# single_DPswap.net
KiCad netlist of a schematic drawn in EAGLE
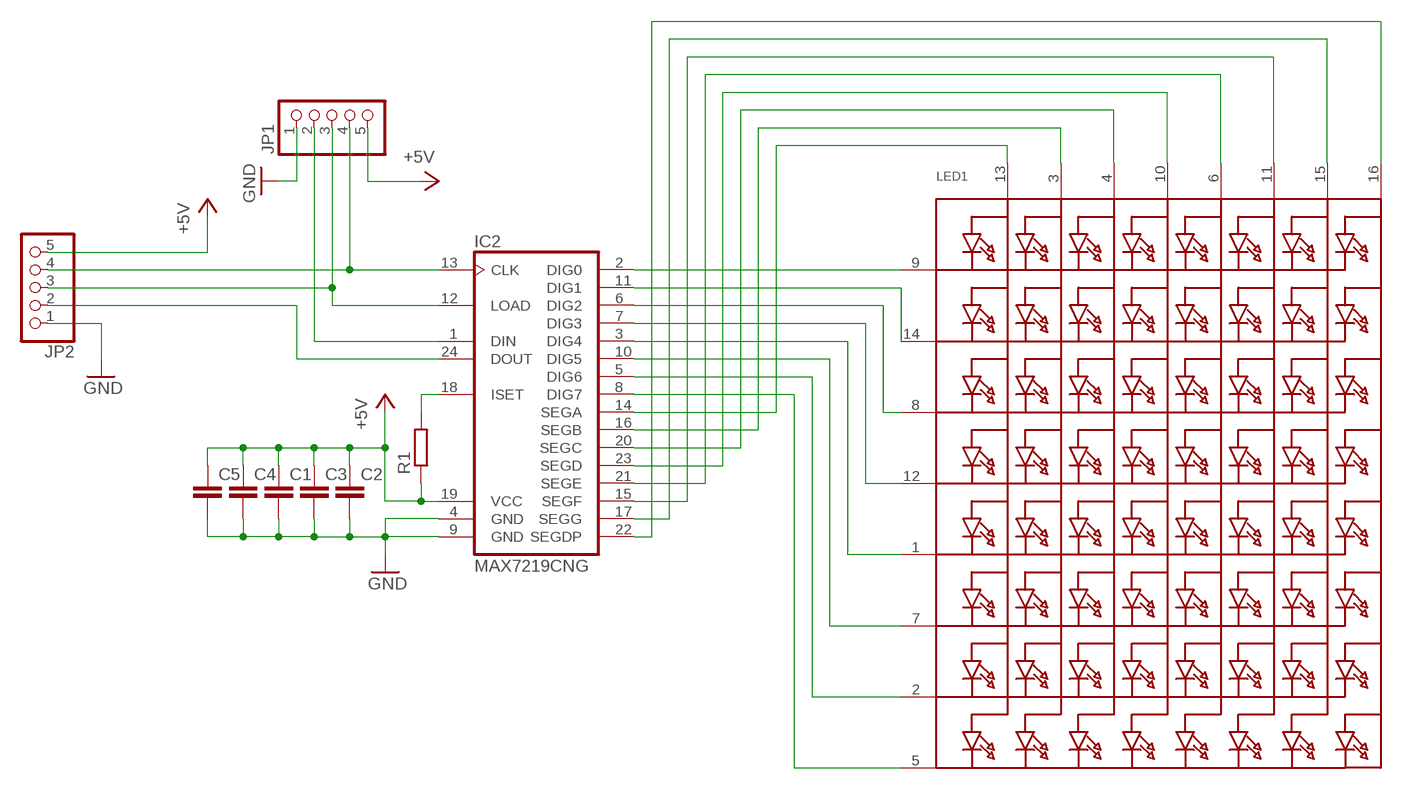
[diagram p0: schematic, sheet 1]

(export (version "E")
  (design (tool "Eeschema 10.0.6"))
  (components
    (comp (ref "C1")
      (value "C-EUC0805K")
      (footprint "eagle-import:C0805K")
      (libsource (lib "eagle-import") (part "C-EUC0805K"))
    )
    (comp (ref "C2")
      (value "C-EUC0805K")
      (footprint "eagle-import:C0805K")
      (libsource (lib "eagle-import") (part "C-EUC0805K"))
    )
    (comp (ref "C3")
      (value "C-EUC0805K")
      (footprint "eagle-import:C0805K")
      (libsource (lib "eagle-import") (part "C-EUC0805K"))
    )
    (comp (ref "C4")
      (value "C-EUC0805K")
      (footprint "eagle-import:C0805K")
      (libsource (lib "eagle-import") (part "C-EUC0805K"))
    )
    (comp (ref "C5")
      (value "C-EUC0805K")
      (footprint "eagle-import:C0805K")
      (libsource (lib "eagle-import") (part "C-EUC0805K"))
    )
    (comp (ref "IC2")
      (value "MAX7219CNG")
      (footprint "eagle-import:DIL24-3")
      (fields (field (name "MF") "MAXIM"))
      (libsource (lib "eagle-import") (part "MAX7219CNG"))
    )
    (comp (ref "JP1")
      (value "PINHD-1X5/90")
      (footprint "eagle-import:1X05_90")
      (libsource (lib "eagle-import") (part "PINHD-1X5/90"))
    )
    (comp (ref "JP2")
      (value "PINHD-1X5/90")
      (footprint "eagle-import:1X05_90")
      (libsource (lib "eagle-import") (part "PINHD-1X5/90"))
    )
    (comp (ref "LED1")
      (value "SEGMENT_8X8_ROWCATHODEM12A881UR")
      (footprint "eagle-import:SEGMENT_BL-M12A881UR")
      (libsource (lib "eagle-import") (part "SEGMENT_8X8_ROWCATHODEM12A881UR"))
    )
    (comp (ref "R1")
      (value "R-EU_M0805")
      (footprint "eagle-import:M0805")
      (libsource (lib "eagle-import") (part "R-EU_M0805"))
    )
  )
  (nets
    (net (code "1") (name "+5V") (class "Default")
      (node (ref "C1") (pin "1") (pinfunction "1_1") (pintype "passive"))
      (node (ref "C2") (pin "1") (pinfunction "1_1") (pintype "passive"))
      (node (ref "C3") (pin "1") (pinfunction "1_1") (pintype "passive"))
      (node (ref "C4") (pin "1") (pinfunction "1_1") (pintype "passive"))
      (node (ref "C5") (pin "1") (pinfunction "1_1") (pintype "passive"))
      (node (ref "IC2") (pin "19") (pinfunction "VCC_19") (pintype "power_in"))
      (node (ref "JP1") (pin "5") (pinfunction "5_5") (pintype "passive"))
      (node (ref "JP2") (pin "5") (pinfunction "5_5") (pintype "passive"))
      (node (ref "R1") (pin "1") (pinfunction "1_1") (pintype "passive"))
    )
    (net (code "2") (name "GND") (class "Default")
      (node (ref "C1") (pin "2") (pinfunction "2_2") (pintype "passive"))
      (node (ref "C2") (pin "2") (pinfunction "2_2") (pintype "passive"))
      (node (ref "C3") (pin "2") (pinfunction "2_2") (pintype "passive"))
      (node (ref "C4") (pin "2") (pinfunction "2_2") (pintype "passive"))
      (node (ref "C5") (pin "2") (pinfunction "2_2") (pintype "passive"))
      (node (ref "IC2") (pin "4") (pinfunction "GND_4") (pintype "power_in"))
      (node (ref "IC2") (pin "9") (pinfunction "GND_9") (pintype "power_in"))
      (node (ref "JP1") (pin "1") (pinfunction "1_1") (pintype "passive"))
      (node (ref "JP2") (pin "1") (pinfunction "1_1") (pintype "passive"))
    )
    (net (code "3") (name "Net-(IC2-CLK)") (class "Default")
      (node (ref "IC2") (pin "13") (pinfunction "CLK_13") (pintype "input"))
      (node (ref "JP1") (pin "4") (pinfunction "4_4") (pintype "passive"))
      (node (ref "JP2") (pin "4") (pinfunction "4_4") (pintype "passive"))
    )
    (net (code "4") (name "Net-(IC2-DIG0)") (class "Default")
      (node (ref "IC2") (pin "2") (pinfunction "DIG0_2") (pintype "output"))
      (node (ref "LED1") (pin "9") (pinfunction "K1_9") (pintype "bidirectional"))
    )
    (net (code "5") (name "Net-(IC2-DIG1)") (class "Default")
      (node (ref "IC2") (pin "11") (pinfunction "DIG1_11") (pintype "output"))
      (node (ref "LED1") (pin "14") (pinfunction "K2_14") (pintype "bidirectional"))
    )
    (net (code "6") (name "Net-(IC2-DIG2)") (class "Default")
      (node (ref "IC2") (pin "6") (pinfunction "DIG2_6") (pintype "output"))
      (node (ref "LED1") (pin "8") (pinfunction "K3_8") (pintype "bidirectional"))
    )
    (net (code "7") (name "Net-(IC2-DIG3)") (class "Default")
      (node (ref "IC2") (pin "7") (pinfunction "DIG3_7") (pintype "output"))
      (node (ref "LED1") (pin "12") (pinfunction "K4_12") (pintype "bidirectional"))
    )
    (net (code "8") (name "Net-(IC2-DIG4)") (class "Default")
      (node (ref "IC2") (pin "3") (pinfunction "DIG4_3") (pintype "output"))
      (node (ref "LED1") (pin "1") (pinfunction "K5_1") (pintype "bidirectional"))
    )
    (net (code "9") (name "Net-(IC2-DIG5)") (class "Default")
      (node (ref "IC2") (pin "10") (pinfunction "DIG5_10") (pintype "output"))
      (node (ref "LED1") (pin "7") (pinfunction "K6_7") (pintype "bidirectional"))
    )
    (net (code "10") (name "Net-(IC2-DIG6)") (class "Default")
      (node (ref "IC2") (pin "5") (pinfunction "DIG6_5") (pintype "output"))
      (node (ref "LED1") (pin "2") (pinfunction "K7_2") (pintype "bidirectional"))
    )
    (net (code "11") (name "Net-(IC2-DIG7)") (class "Default")
      (node (ref "IC2") (pin "8") (pinfunction "DIG7_8") (pintype "output"))
      (node (ref "LED1") (pin "5") (pinfunction "K8_5") (pintype "bidirectional"))
    )
    (net (code "12") (name "Net-(IC2-DIN)") (class "Default")
      (node (ref "IC2") (pin "1") (pinfunction "DIN_1") (pintype "input"))
      (node (ref "JP1") (pin "2") (pinfunction "2_2") (pintype "passive"))
    )
    (net (code "13") (name "Net-(IC2-DOUT)") (class "Default")
      (node (ref "IC2") (pin "24") (pinfunction "DOUT_24") (pintype "output"))
      (node (ref "JP2") (pin "2") (pinfunction "2_2") (pintype "passive"))
    )
    (net (code "14") (name "Net-(IC2-ISET)") (class "Default")
      (node (ref "IC2") (pin "18") (pinfunction "ISET_18") (pintype "input"))
      (node (ref "R1") (pin "2") (pinfunction "2_2") (pintype "passive"))
    )
    (net (code "15") (name "Net-(IC2-LOAD)") (class "Default")
      (node (ref "IC2") (pin "12") (pinfunction "LOAD_12") (pintype "input"))
      (node (ref "JP1") (pin "3") (pinfunction "3_3") (pintype "passive"))
      (node (ref "JP2") (pin "3") (pinfunction "3_3") (pintype "passive"))
    )
    (net (code "16") (name "Net-(IC2-SEGA)") (class "Default")
      (node (ref "IC2") (pin "14") (pinfunction "SEGA_14") (pintype "output"))
      (node (ref "LED1") (pin "13") (pinfunction "A1_13") (pintype "bidirectional"))
    )
    (net (code "17") (name "Net-(IC2-SEGB)") (class "Default")
      (node (ref "IC2") (pin "16") (pinfunction "SEGB_16") (pintype "output"))
      (node (ref "LED1") (pin "3") (pinfunction "A2_3") (pintype "bidirectional"))
    )
    (net (code "18") (name "Net-(IC2-SEGC)") (class "Default")
      (node (ref "IC2") (pin "20") (pinfunction "SEGC_20") (pintype "output"))
      (node (ref "LED1") (pin "4") (pinfunction "A3_4") (pintype "bidirectional"))
    )
    (net (code "19") (name "Net-(IC2-SEGD)") (class "Default")
      (node (ref "IC2") (pin "23") (pinfunction "SEGD_23") (pintype "output"))
      (node (ref "LED1") (pin "10") (pinfunction "A4_10") (pintype "bidirectional"))
    )
    (net (code "20") (name "Net-(IC2-SEGDP)") (class "Default")
      (node (ref "IC2") (pin "22") (pinfunction "SEGDP_22") (pintype "output"))
      (node (ref "LED1") (pin "16") (pinfunction "A8_16") (pintype "bidirectional"))
    )
    (net (code "21") (name "Net-(IC2-SEGE)") (class "Default")
      (node (ref "IC2") (pin "21") (pinfunction "SEGE_21") (pintype "output"))
      (node (ref "LED1") (pin "6") (pinfunction "A5_6") (pintype "bidirectional"))
    )
    (net (code "22") (name "Net-(IC2-SEGF)") (class "Default")
      (node (ref "IC2") (pin "15") (pinfunction "SEGF_15") (pintype "output"))
      (node (ref "LED1") (pin "11") (pinfunction "A6_11") (pintype "bidirectional"))
    )
    (net (code "23") (name "Net-(IC2-SEGG)") (class "Default")
      (node (ref "IC2") (pin "17") (pinfunction "SEGG_17") (pintype "output"))
      (node (ref "LED1") (pin "15") (pinfunction "A7_15") (pintype "bidirectional"))
    )
  )
)
